# DAC.net
KiCad netlist of a schematic drawn in Altium Designer
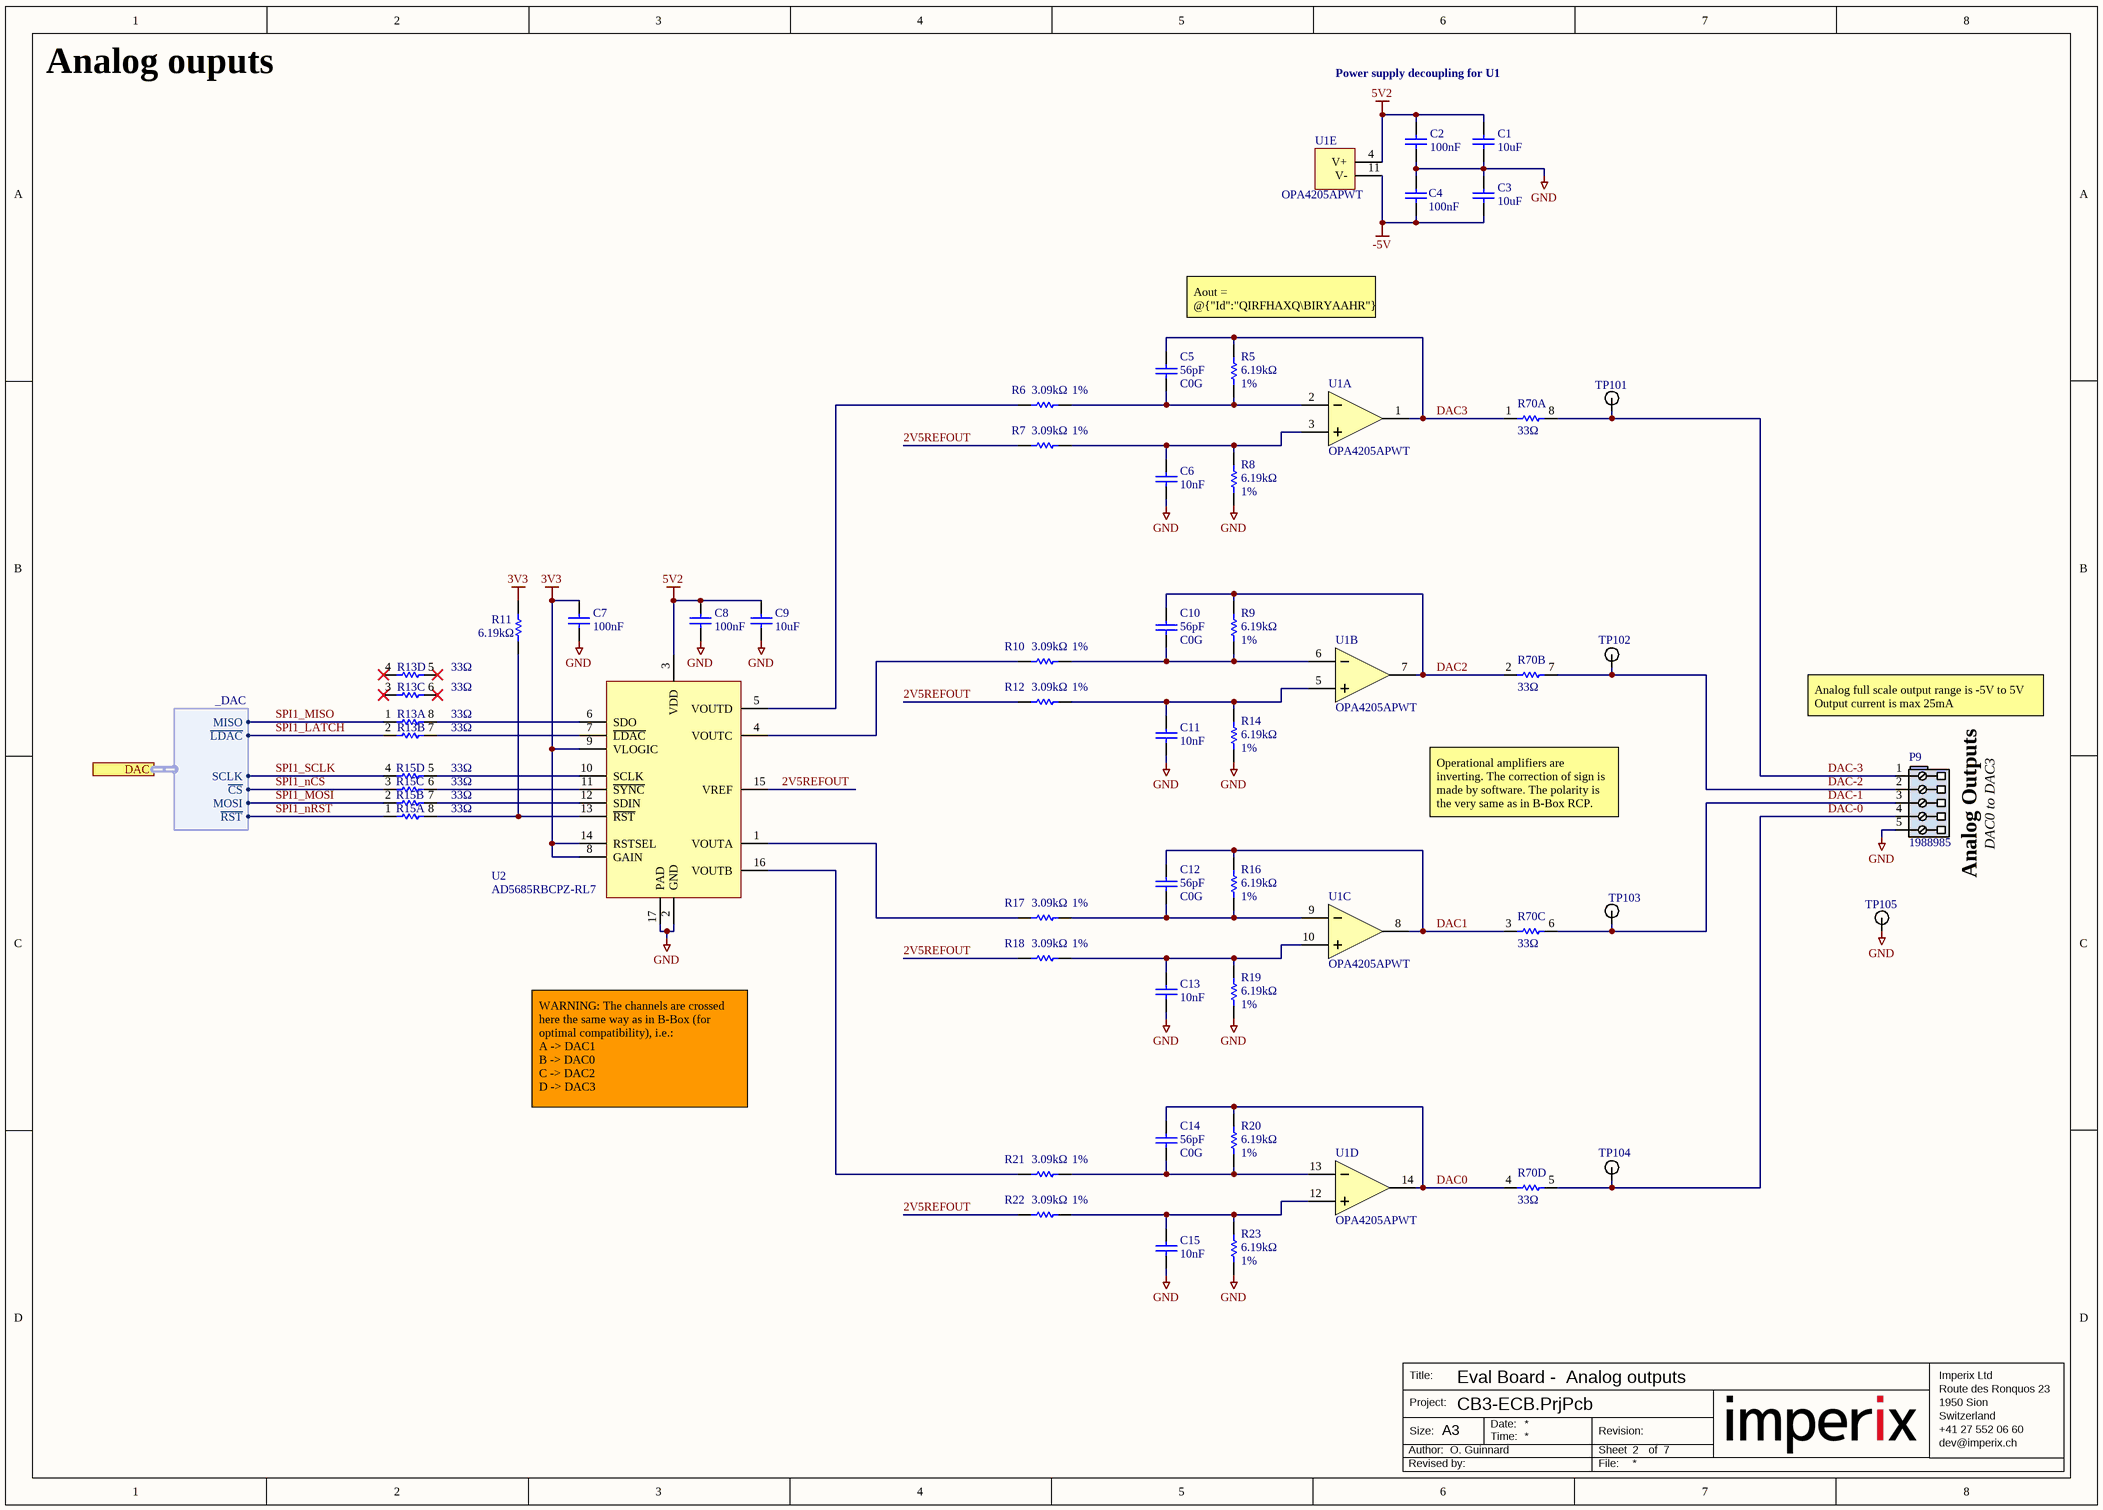
[diagram p0: DAC.SchDoc]

(export (version "E")
  (design (tool "Eeschema 10.0.6"))
  (components
    (comp (ref "C1")
      (value "10uF")
      (footprint "CAPC1608L(0603)")
      (description "CAP CER 10UF 10V X5R 0603 10% (Generic Imperix Component)")
      (fields (field (name "TOLERANCE") "10%") (field (name "Comment") "CAP-10UF-10V-X5R-0603-10%"))
      (libsource (lib "CB3-ECB") (part "Capacitor non-polarized"))
    )
    (comp (ref "C2")
      (value "100nF")
      (footprint "CAPC1005L(0402)")
      (description "CAP CER 100NF 25V X7R 0402 10% (Generic Imperix Component)")
      (fields (field (name "TOLERANCE") "10%") (field (name "Comment") "CAP-100NF-25V-X7R-0402-10%"))
      (libsource (lib "CB3-ECB") (part "Capacitor non-polarized"))
    )
    (comp (ref "C3")
      (value "10uF")
      (footprint "CAPC1608L(0603)")
      (description "CAP CER 10UF 10V X5R 0603 10% (Generic Imperix Component)")
      (fields (field (name "TOLERANCE") "10%") (field (name "Comment") "CAP-10UF-10V-X5R-0603-10%"))
      (libsource (lib "CB3-ECB") (part "Capacitor non-polarized"))
    )
    (comp (ref "C4")
      (value "100nF")
      (footprint "CAPC1005L(0402)")
      (description "CAP CER 100NF 25V X7R 0402 10% (Generic Imperix Component)")
      (fields (field (name "TOLERANCE") "10%") (field (name "Comment") "CAP-100NF-25V-X7R-0402-10%"))
      (libsource (lib "CB3-ECB") (part "Capacitor non-polarized"))
    )
    (comp (ref "C5")
      (value "56pF")
      (footprint "CAPC1005L(0402)")
      (description "CAP CER 56PF 50V C0G 0402 1% (Generic Imperix Component)")
      (fields
        (field (name "TOLERANCE") "1%")
        (field (name "DIELECTRIC") "C0G")
        (field (name "Comment") "CAP-56PF-50V-C0G-0402-1%")
      )
      (libsource (lib "CB3-ECB") (part "Capacitor non-polarized"))
    )
    (comp (ref "C6")
      (value "10nF")
      (footprint "CAPC1005L(0402)")
      (description "CAP CER 10NF 25V X7R 0402 10% (Generic Imperix Component)")
      (fields (field (name "TOLERANCE") "10%") (field (name "Comment") "CAP-10NF-25V-X7R-0402-10%"))
      (libsource (lib "CB3-ECB") (part "Capacitor non-polarized"))
    )
    (comp (ref "C7")
      (value "100nF")
      (footprint "CAPC1005L(0402)")
      (description "CAP CER 100NF 25V X7R 0402 10% (Generic Imperix Component)")
      (fields (field (name "TOLERANCE") "10%") (field (name "Comment") "CAP-100NF-25V-X7R-0402-10%"))
      (libsource (lib "CB3-ECB") (part "Capacitor non-polarized"))
    )
    (comp (ref "C8")
      (value "100nF")
      (footprint "CAPC1005L(0402)")
      (description "CAP CER 100NF 25V X7R 0402 10% (Generic Imperix Component)")
      (fields (field (name "TOLERANCE") "10%") (field (name "Comment") "CAP-100NF-25V-X7R-0402-10%"))
      (libsource (lib "CB3-ECB") (part "Capacitor non-polarized"))
    )
    (comp (ref "C9")
      (value "10uF")
      (footprint "CAPC1608L(0603)")
      (description "CAP CER 10UF 10V X5R 0603 10% (Generic Imperix Component)")
      (fields (field (name "TOLERANCE") "10%") (field (name "Comment") "CAP-10UF-10V-X5R-0603-10%"))
      (libsource (lib "CB3-ECB") (part "Capacitor non-polarized"))
    )
    (comp (ref "C10")
      (value "56pF")
      (footprint "CAPC1005L(0402)")
      (description "CAP CER 56PF 50V C0G 0402 1% (Generic Imperix Component)")
      (fields
        (field (name "TOLERANCE") "1%")
        (field (name "DIELECTRIC") "C0G")
        (field (name "Comment") "CAP-56PF-50V-C0G-0402-1%")
      )
      (libsource (lib "CB3-ECB") (part "Capacitor non-polarized"))
    )
    (comp (ref "C11")
      (value "10nF")
      (footprint "CAPC1005L(0402)")
      (description "CAP CER 10NF 25V X7R 0402 10% (Generic Imperix Component)")
      (fields (field (name "TOLERANCE") "10%") (field (name "Comment") "CAP-10NF-25V-X7R-0402-10%"))
      (libsource (lib "CB3-ECB") (part "Capacitor non-polarized"))
    )
    (comp (ref "C12")
      (value "56pF")
      (footprint "CAPC1005L(0402)")
      (description "CAP CER 56PF 50V C0G 0402 1% (Generic Imperix Component)")
      (fields
        (field (name "TOLERANCE") "1%")
        (field (name "DIELECTRIC") "C0G")
        (field (name "Comment") "CAP-56PF-50V-C0G-0402-1%")
      )
      (libsource (lib "CB3-ECB") (part "Capacitor non-polarized"))
    )
    (comp (ref "C13")
      (value "10nF")
      (footprint "CAPC1005L(0402)")
      (description "CAP CER 10NF 25V X7R 0402 10% (Generic Imperix Component)")
      (fields (field (name "TOLERANCE") "10%") (field (name "Comment") "CAP-10NF-25V-X7R-0402-10%"))
      (libsource (lib "CB3-ECB") (part "Capacitor non-polarized"))
    )
    (comp (ref "C14")
      (value "56pF")
      (footprint "CAPC1005L(0402)")
      (description "CAP CER 56PF 50V C0G 0402 1% (Generic Imperix Component)")
      (fields
        (field (name "TOLERANCE") "1%")
        (field (name "DIELECTRIC") "C0G")
        (field (name "Comment") "CAP-56PF-50V-C0G-0402-1%")
      )
      (libsource (lib "CB3-ECB") (part "Capacitor non-polarized"))
    )
    (comp (ref "C15")
      (value "10nF")
      (footprint "CAPC1005L(0402)")
      (description "CAP CER 10NF 25V X7R 0402 10% (Generic Imperix Component)")
      (fields (field (name "TOLERANCE") "10%") (field (name "Comment") "CAP-10NF-25V-X7R-0402-10%"))
      (libsource (lib "CB3-ECB") (part "Capacitor non-polarized"))
    )
    (comp (ref "P9")
      (value "1988985")
      (footprint "1988985")
      (description "Conn PC Terminal Block 5 POS 3.5mm Solder Thru-Hole 17.5A")
      (fields (field (name "VOLTAGE") "300V"))
      (libsource (lib "CB3-ECB") (part "1988985"))
    )
    (comp (ref "R5")
      (value "6.19kΩ")
      (footprint "RESC1005L(0402)")
      (description "RES SMD 6.19KΩ 1/16W 100PPM 0402 1% (Generic Imperix Component)")
      (fields (field (name "TOLERANCE") "1%") (field (name "Comment") "RES-6.19KΩ-1/16W-100PPM-0402-1%"))
      (libsource (lib "CB3-ECB") (part "Resistor"))
    )
    (comp (ref "R6")
      (value "3.09kΩ")
      (footprint "RESC1005L(0402)")
      (description "RES SMD 3.09KΩ 1/16W 100PPM 0402 1% (Generic Imperix Component)")
      (fields (field (name "TOLERANCE") "1%") (field (name "Comment") "RES-3.09KΩ-1/16W-100PPM-0402-1%"))
      (libsource (lib "CB3-ECB") (part "Resistor"))
    )
    (comp (ref "R7")
      (value "3.09kΩ")
      (footprint "RESC1005L(0402)")
      (description "RES SMD 3.09KΩ 1/16W 100PPM 0402 1% (Generic Imperix Component)")
      (fields (field (name "TOLERANCE") "1%") (field (name "Comment") "RES-3.09KΩ-1/16W-100PPM-0402-1%"))
      (libsource (lib "CB3-ECB") (part "Resistor"))
    )
    (comp (ref "R8")
      (value "6.19kΩ")
      (footprint "RESC1005L(0402)")
      (description "RES SMD 6.19KΩ 1/16W 100PPM 0402 1% (Generic Imperix Component)")
      (fields (field (name "TOLERANCE") "1%") (field (name "Comment") "RES-6.19KΩ-1/16W-100PPM-0402-1%"))
      (libsource (lib "CB3-ECB") (part "Resistor"))
    )
    (comp (ref "R9")
      (value "6.19kΩ")
      (footprint "RESC1005L(0402)")
      (description "RES SMD 6.19KΩ 1/16W 100PPM 0402 1% (Generic Imperix Component)")
      (fields (field (name "TOLERANCE") "1%") (field (name "Comment") "RES-6.19KΩ-1/16W-100PPM-0402-1%"))
      (libsource (lib "CB3-ECB") (part "Resistor"))
    )
    (comp (ref "R10")
      (value "3.09kΩ")
      (footprint "RESC1005L(0402)")
      (description "RES SMD 3.09KΩ 1/16W 100PPM 0402 1% (Generic Imperix Component)")
      (fields (field (name "TOLERANCE") "1%") (field (name "Comment") "RES-3.09KΩ-1/16W-100PPM-0402-1%"))
      (libsource (lib "CB3-ECB") (part "Resistor"))
    )
    (comp (ref "R11")
      (value "6.19kΩ")
      (footprint "RESC1005L(0402)")
      (description "RES SMD 6.19KΩ 1/16W 100PPM 0402 1% (Generic Imperix Component)")
      (fields (field (name "TOLERANCE") "1%") (field (name "Comment") "RES-6.19KΩ-1/16W-100PPM-0402-1%"))
      (libsource (lib "CB3-ECB") (part "Resistor"))
    )
    (comp (ref "R12")
      (value "3.09kΩ")
      (footprint "RESC1005L(0402)")
      (description "RES SMD 3.09KΩ 1/16W 100PPM 0402 1% (Generic Imperix Component)")
      (fields (field (name "TOLERANCE") "1%") (field (name "Comment") "RES-3.09KΩ-1/16W-100PPM-0402-1%"))
      (libsource (lib "CB3-ECB") (part "Resistor"))
    )
    (comp (ref "R13")
      (value "33Ω")
      (footprint "RESQUAD0804")
      (description "Res Thick Film Array 33 Ohm 5% ±200ppm/°C ISOL 8-Pin 0804(4 X 0402) Convex SMD Automotive T/R")
      (fields (field (name "TOLERANCE") "5%") (field (name "Comment") "EXB-28V330JX"))
      (libsource (lib "CB3-ECB") (part "Resistor Array Quad"))
    )
    (comp (ref "R14")
      (value "6.19kΩ")
      (footprint "RESC1005L(0402)")
      (description "RES SMD 6.19KΩ 1/16W 100PPM 0402 1% (Generic Imperix Component)")
      (fields (field (name "TOLERANCE") "1%") (field (name "Comment") "RES-6.19KΩ-1/16W-100PPM-0402-1%"))
      (libsource (lib "CB3-ECB") (part "Resistor"))
    )
    (comp (ref "R15")
      (value "33Ω")
      (footprint "RESQUAD0804")
      (description "Res Thick Film Array 33 Ohm 5% ±200ppm/°C ISOL 8-Pin 0804(4 X 0402) Convex SMD Automotive T/R")
      (fields (field (name "TOLERANCE") "5%") (field (name "Comment") "EXB-28V330JX"))
      (libsource (lib "CB3-ECB") (part "Resistor Array Quad"))
    )
    (comp (ref "R16")
      (value "6.19kΩ")
      (footprint "RESC1005L(0402)")
      (description "RES SMD 6.19KΩ 1/16W 100PPM 0402 1% (Generic Imperix Component)")
      (fields (field (name "TOLERANCE") "1%") (field (name "Comment") "RES-6.19KΩ-1/16W-100PPM-0402-1%"))
      (libsource (lib "CB3-ECB") (part "Resistor"))
    )
    (comp (ref "R17")
      (value "3.09kΩ")
      (footprint "RESC1005L(0402)")
      (description "RES SMD 3.09KΩ 1/16W 100PPM 0402 1% (Generic Imperix Component)")
      (fields (field (name "TOLERANCE") "1%") (field (name "Comment") "RES-3.09KΩ-1/16W-100PPM-0402-1%"))
      (libsource (lib "CB3-ECB") (part "Resistor"))
    )
    (comp (ref "R18")
      (value "3.09kΩ")
      (footprint "RESC1005L(0402)")
      (description "RES SMD 3.09KΩ 1/16W 100PPM 0402 1% (Generic Imperix Component)")
      (fields (field (name "TOLERANCE") "1%") (field (name "Comment") "RES-3.09KΩ-1/16W-100PPM-0402-1%"))
      (libsource (lib "CB3-ECB") (part "Resistor"))
    )
    (comp (ref "R19")
      (value "6.19kΩ")
      (footprint "RESC1005L(0402)")
      (description "RES SMD 6.19KΩ 1/16W 100PPM 0402 1% (Generic Imperix Component)")
      (fields (field (name "TOLERANCE") "1%") (field (name "Comment") "RES-6.19KΩ-1/16W-100PPM-0402-1%"))
      (libsource (lib "CB3-ECB") (part "Resistor"))
    )
    (comp (ref "R20")
      (value "6.19kΩ")
      (footprint "RESC1005L(0402)")
      (description "RES SMD 6.19KΩ 1/16W 100PPM 0402 1% (Generic Imperix Component)")
      (fields (field (name "TOLERANCE") "1%") (field (name "Comment") "RES-6.19KΩ-1/16W-100PPM-0402-1%"))
      (libsource (lib "CB3-ECB") (part "Resistor"))
    )
    (comp (ref "R21")
      (value "3.09kΩ")
      (footprint "RESC1005L(0402)")
      (description "RES SMD 3.09KΩ 1/16W 100PPM 0402 1% (Generic Imperix Component)")
      (fields (field (name "TOLERANCE") "1%") (field (name "Comment") "RES-3.09KΩ-1/16W-100PPM-0402-1%"))
      (libsource (lib "CB3-ECB") (part "Resistor"))
    )
    (comp (ref "R22")
      (value "3.09kΩ")
      (footprint "RESC1005L(0402)")
      (description "RES SMD 3.09KΩ 1/16W 100PPM 0402 1% (Generic Imperix Component)")
      (fields (field (name "TOLERANCE") "1%") (field (name "Comment") "RES-3.09KΩ-1/16W-100PPM-0402-1%"))
      (libsource (lib "CB3-ECB") (part "Resistor"))
    )
    (comp (ref "R23")
      (value "6.19kΩ")
      (footprint "RESC1005L(0402)")
      (description "RES SMD 6.19KΩ 1/16W 100PPM 0402 1% (Generic Imperix Component)")
      (fields (field (name "TOLERANCE") "1%") (field (name "Comment") "RES-6.19KΩ-1/16W-100PPM-0402-1%"))
      (libsource (lib "CB3-ECB") (part "Resistor"))
    )
    (comp (ref "R70")
      (value "33Ω")
      (footprint "RESQUAD0804")
      (description "Res Thick Film Array 33 Ohm 5% ±200ppm/°C ISOL 8-Pin 0804(4 X 0402) Convex SMD Automotive T/R")
      (fields (field (name "TOLERANCE") "5%") (field (name "Comment") "EXB-28V330JX"))
      (libsource (lib "CB3-ECB") (part "Resistor Array Quad"))
    )
    (comp (ref "TP101")
      (value "5001")
      (footprint "5001")
      (description "Black PC Test Point, Miniature Phosphor Bronze Silver Plating Through Hole Mounting Type")
      (libsource (lib "CB3-ECB") (part "Testpoint"))
    )
    (comp (ref "TP102")
      (value "5001")
      (footprint "5001")
      (description "Black PC Test Point, Miniature Phosphor Bronze Silver Plating Through Hole Mounting Type")
      (libsource (lib "CB3-ECB") (part "Testpoint"))
    )
    (comp (ref "TP103")
      (value "5001")
      (footprint "5001")
      (description "Black PC Test Point, Miniature Phosphor Bronze Silver Plating Through Hole Mounting Type")
      (libsource (lib "CB3-ECB") (part "Testpoint"))
    )
    (comp (ref "TP104")
      (value "5001")
      (footprint "5001")
      (description "Black PC Test Point, Miniature Phosphor Bronze Silver Plating Through Hole Mounting Type")
      (libsource (lib "CB3-ECB") (part "Testpoint"))
    )
    (comp (ref "TP105")
      (value "5001")
      (footprint "5001")
      (description "Black PC Test Point, Miniature Phosphor Bronze Silver Plating Through Hole Mounting Type")
      (libsource (lib "CB3-ECB") (part "Testpoint"))
    )
    (comp (ref "U1")
      (value "OPA4205APWT")
      (footprint "TSSOP65P640-14N")
      (libsource (lib "") (part "Quad Op-Amp_1"))
    )
    (comp (ref "U2")
      (value "AD5685RBCPZ-RL7")
      (footprint "QFN50P300X300-16WAL")
      (description "DAC 4-CH Resistor-String 14-bit 16-Pin LFCSP EP T/R")
      (libsource (lib "CB3-ECB") (part "AD5685RBCPZ-RL7"))
    )
  )
  (nets
    (net (code "2") (name "-5V") (class "Default")
      (node (ref "C3") (pin "1") (pinfunction "1_1") (pintype "passive"))
      (node (ref "C4") (pin "1") (pinfunction "1_1") (pintype "passive"))
      (node (ref "U1") (pin "11") (pinfunction "V-_11") (pintype "power_in"))
    )
    (net (code "3") (name "/2V5REFOUT") (class "Default")
      (node (ref "R12") (pin "2") (pinfunction "2_2") (pintype "passive"))
      (node (ref "R18") (pin "2") (pinfunction "2_2") (pintype "passive"))
      (node (ref "R22") (pin "2") (pinfunction "2_2") (pintype "passive"))
      (node (ref "R7") (pin "2") (pinfunction "2_2") (pintype "passive"))
      (node (ref "U2") (pin "15") (pinfunction "VREF_15") (pintype "passive"))
    )
    (net (code "4") (name "/DAC-0") (class "Default")
      (node (ref "P9") (pin "4") (pinfunction "4_4") (pintype "passive"))
      (node (ref "R70") (pin "5") (pinfunction "5_5") (pintype "passive"))
      (node (ref "TP104") (pin "1") (pinfunction "TP_1") (pintype "passive"))
    )
    (net (code "5") (name "/DAC-1") (class "Default")
      (node (ref "P9") (pin "3") (pinfunction "3_3") (pintype "passive"))
      (node (ref "R70") (pin "6") (pinfunction "6_6") (pintype "passive"))
      (node (ref "TP103") (pin "1") (pinfunction "TP_1") (pintype "passive"))
    )
    (net (code "6") (name "/DAC-2") (class "Default")
      (node (ref "P9") (pin "2") (pinfunction "2_2") (pintype "passive"))
      (node (ref "R70") (pin "7") (pinfunction "7_7") (pintype "passive"))
      (node (ref "TP102") (pin "1") (pinfunction "TP_1") (pintype "passive"))
    )
    (net (code "7") (name "/DAC-3") (class "Default")
      (node (ref "P9") (pin "1") (pinfunction "1_1") (pintype "passive"))
      (node (ref "R70") (pin "8") (pinfunction "8_8") (pintype "passive"))
      (node (ref "TP101") (pin "1") (pinfunction "TP_1") (pintype "passive"))
    )
    (net (code "8") (name "/DAC0") (class "Default")
      (node (ref "C14") (pin "2") (pinfunction "2_2") (pintype "passive"))
      (node (ref "R20") (pin "2") (pinfunction "2_2") (pintype "passive"))
      (node (ref "R70") (pin "4") (pinfunction "4_4") (pintype "passive"))
      (node (ref "U1") (pin "14") (pinfunction "OUT_14") (pintype "passive"))
    )
    (net (code "9") (name "/DAC1") (class "Default")
      (node (ref "C12") (pin "2") (pinfunction "2_2") (pintype "passive"))
      (node (ref "R16") (pin "2") (pinfunction "2_2") (pintype "passive"))
      (node (ref "R70") (pin "3") (pinfunction "3_3") (pintype "passive"))
      (node (ref "U1") (pin "8") (pinfunction "OUT_8") (pintype "passive"))
    )
    (net (code "10") (name "/DAC2") (class "Default")
      (node (ref "C10") (pin "2") (pinfunction "2_2") (pintype "passive"))
      (node (ref "R70") (pin "2") (pinfunction "2_2") (pintype "passive"))
      (node (ref "R9") (pin "2") (pinfunction "2_2") (pintype "passive"))
      (node (ref "U1") (pin "7") (pinfunction "OUT_7") (pintype "passive"))
    )
    (net (code "11") (name "/DAC3") (class "Default")
      (node (ref "C5") (pin "2") (pinfunction "2_2") (pintype "passive"))
      (node (ref "R5") (pin "2") (pinfunction "2_2") (pintype "passive"))
      (node (ref "R70") (pin "1") (pinfunction "1_1") (pintype "passive"))
      (node (ref "U1") (pin "1") (pinfunction "OUT_1") (pintype "passive"))
    )
    (net (code "12") (name "/SPI1_LATCH") (class "Default")
      (node (ref "R13") (pin "2") (pinfunction "2_2") (pintype "passive"))
    )
    (net (code "13") (name "/SPI1_MISO") (class "Default")
      (node (ref "R13") (pin "1") (pinfunction "1_1") (pintype "passive"))
    )
    (net (code "14") (name "/SPI1_MOSI") (class "Default")
      (node (ref "R15") (pin "2") (pinfunction "2_2") (pintype "passive"))
    )
    (net (code "15") (name "/SPI1_SCLK") (class "Default")
      (node (ref "R15") (pin "4") (pinfunction "4_4") (pintype "passive"))
    )
    (net (code "16") (name "/SPI1_nCS") (class "Default")
      (node (ref "R15") (pin "3") (pinfunction "3_3") (pintype "passive"))
    )
    (net (code "17") (name "/SPI1_nRST") (class "Default")
      (node (ref "R15") (pin "1") (pinfunction "1_1") (pintype "passive"))
    )
    (net (code "19") (name "3V3") (class "Default")
      (node (ref "C7") (pin "2") (pinfunction "2_2") (pintype "passive"))
      (node (ref "R11") (pin "2") (pinfunction "2_2") (pintype "passive"))
      (node (ref "U2") (pin "14") (pinfunction "RSTSEL_14") (pintype "passive"))
      (node (ref "U2") (pin "8") (pinfunction "GAIN_8") (pintype "passive"))
      (node (ref "U2") (pin "9") (pinfunction "VLOGIC_9") (pintype "passive"))
    )
    (net (code "20") (name "5V2") (class "Default")
      (node (ref "C1") (pin "2") (pinfunction "2_2") (pintype "passive"))
      (node (ref "C2") (pin "2") (pinfunction "2_2") (pintype "passive"))
      (node (ref "C8") (pin "2") (pinfunction "2_2") (pintype "passive"))
      (node (ref "C9") (pin "2") (pinfunction "2_2") (pintype "passive"))
      (node (ref "U1") (pin "4") (pinfunction "V+_4") (pintype "power_in"))
      (node (ref "U2") (pin "3") (pinfunction "VDD_3") (pintype "passive"))
    )
    (net (code "21") (name "GND") (class "Default")
      (node (ref "C1") (pin "1") (pinfunction "1_1") (pintype "passive"))
      (node (ref "C11") (pin "1") (pinfunction "1_1") (pintype "passive"))
      (node (ref "C13") (pin "1") (pinfunction "1_1") (pintype "passive"))
      (node (ref "C15") (pin "1") (pinfunction "1_1") (pintype "passive"))
      (node (ref "C2") (pin "1") (pinfunction "1_1") (pintype "passive"))
      (node (ref "C3") (pin "2") (pinfunction "2_2") (pintype "passive"))
      (node (ref "C4") (pin "2") (pinfunction "2_2") (pintype "passive"))
      (node (ref "C6") (pin "1") (pinfunction "1_1") (pintype "passive"))
      (node (ref "C7") (pin "1") (pinfunction "1_1") (pintype "passive"))
      (node (ref "C8") (pin "1") (pinfunction "1_1") (pintype "passive"))
      (node (ref "C9") (pin "1") (pinfunction "1_1") (pintype "passive"))
      (node (ref "P9") (pin "5") (pinfunction "5_5") (pintype "passive"))
      (node (ref "R14") (pin "1") (pinfunction "1_1") (pintype "passive"))
      (node (ref "R19") (pin "1") (pinfunction "1_1") (pintype "passive"))
      (node (ref "R23") (pin "1") (pinfunction "1_1") (pintype "passive"))
      (node (ref "R8") (pin "1") (pinfunction "1_1") (pintype "passive"))
      (node (ref "TP105") (pin "1") (pinfunction "TP_1") (pintype "passive"))
      (node (ref "U2") (pin "17") (pinfunction "PAD_17") (pintype "passive"))
      (node (ref "U2") (pin "2") (pinfunction "GND_2") (pintype "passive"))
    )
    (net (code "22") (name "Net-(U1A-IN+)") (class "Default")
      (node (ref "C6") (pin "2") (pinfunction "2_2") (pintype "passive"))
      (node (ref "R7") (pin "1") (pinfunction "1_1") (pintype "passive"))
      (node (ref "R8") (pin "2") (pinfunction "2_2") (pintype "passive"))
      (node (ref "U1") (pin "3") (pinfunction "IN+_3") (pintype "passive"))
    )
    (net (code "23") (name "Net-(U1A-IN-)") (class "Default")
      (node (ref "C5") (pin "1") (pinfunction "1_1") (pintype "passive"))
      (node (ref "R5") (pin "1") (pinfunction "1_1") (pintype "passive"))
      (node (ref "R6") (pin "1") (pinfunction "1_1") (pintype "passive"))
      (node (ref "U1") (pin "2") (pinfunction "IN-_2") (pintype "passive"))
    )
    (net (code "24") (name "Net-(U1B-IN+)") (class "Default")
      (node (ref "C11") (pin "2") (pinfunction "2_2") (pintype "passive"))
      (node (ref "R12") (pin "1") (pinfunction "1_1") (pintype "passive"))
      (node (ref "R14") (pin "2") (pinfunction "2_2") (pintype "passive"))
      (node (ref "U1") (pin "5") (pinfunction "IN+_5") (pintype "passive"))
    )
    (net (code "25") (name "Net-(U1B-IN-)") (class "Default")
      (node (ref "C10") (pin "1") (pinfunction "1_1") (pintype "passive"))
      (node (ref "R10") (pin "1") (pinfunction "1_1") (pintype "passive"))
      (node (ref "R9") (pin "1") (pinfunction "1_1") (pintype "passive"))
      (node (ref "U1") (pin "6") (pinfunction "IN-_6") (pintype "passive"))
    )
    (net (code "26") (name "Net-(U1C-IN+)") (class "Default")
      (node (ref "C13") (pin "2") (pinfunction "2_2") (pintype "passive"))
      (node (ref "R18") (pin "1") (pinfunction "1_1") (pintype "passive"))
      (node (ref "R19") (pin "2") (pinfunction "2_2") (pintype "passive"))
      (node (ref "U1") (pin "10") (pinfunction "IN+_10") (pintype "passive"))
    )
    (net (code "27") (name "Net-(U1C-IN-)") (class "Default")
      (node (ref "C12") (pin "1") (pinfunction "1_1") (pintype "passive"))
      (node (ref "R16") (pin "1") (pinfunction "1_1") (pintype "passive"))
      (node (ref "R17") (pin "1") (pinfunction "1_1") (pintype "passive"))
      (node (ref "U1") (pin "9") (pinfunction "IN-_9") (pintype "passive"))
    )
    (net (code "28") (name "Net-(U1D-IN+)") (class "Default")
      (node (ref "C15") (pin "2") (pinfunction "2_2") (pintype "passive"))
      (node (ref "R22") (pin "1") (pinfunction "1_1") (pintype "passive"))
      (node (ref "R23") (pin "2") (pinfunction "2_2") (pintype "passive"))
      (node (ref "U1") (pin "12") (pinfunction "IN+_12") (pintype "passive"))
    )
    (net (code "29") (name "Net-(U1D-IN-)") (class "Default")
      (node (ref "C14") (pin "1") (pinfunction "1_1") (pintype "passive"))
      (node (ref "R20") (pin "1") (pinfunction "1_1") (pintype "passive"))
      (node (ref "R21") (pin "1") (pinfunction "1_1") (pintype "passive"))
      (node (ref "U1") (pin "13") (pinfunction "IN-_13") (pintype "passive"))
    )
    (net (code "30") (name "Net-(U2-SCLK)") (class "Default")
      (node (ref "R15") (pin "5") (pinfunction "5_5") (pintype "passive"))
      (node (ref "U2") (pin "10") (pinfunction "SCLK_10") (pintype "passive"))
    )
    (net (code "31") (name "Net-(U2-SDIN)") (class "Default")
      (node (ref "R15") (pin "7") (pinfunction "7_7") (pintype "passive"))
      (node (ref "U2") (pin "12") (pinfunction "SDIN_12") (pintype "passive"))
    )
    (net (code "32") (name "Net-(U2-SDO)") (class "Default")
      (node (ref "R13") (pin "8") (pinfunction "8_8") (pintype "passive"))
      (node (ref "U2") (pin "6") (pinfunction "SDO_6") (pintype "passive"))
    )
    (net (code "33") (name "Net-(U2-VOUTA)") (class "Default")
      (node (ref "R17") (pin "2") (pinfunction "2_2") (pintype "passive"))
      (node (ref "U2") (pin "1") (pinfunction "VOUTA_1") (pintype "passive"))
    )
    (net (code "34") (name "Net-(U2-VOUTB)") (class "Default")
      (node (ref "R21") (pin "2") (pinfunction "2_2") (pintype "passive"))
      (node (ref "U2") (pin "16") (pinfunction "VOUTB_16") (pintype "passive"))
    )
    (net (code "35") (name "Net-(U2-VOUTC)") (class "Default")
      (node (ref "R10") (pin "2") (pinfunction "2_2") (pintype "passive"))
      (node (ref "U2") (pin "4") (pinfunction "VOUTC_4") (pintype "passive"))
    )
    (net (code "36") (name "Net-(U2-VOUTD)") (class "Default")
      (node (ref "R6") (pin "2") (pinfunction "2_2") (pintype "passive"))
      (node (ref "U2") (pin "5") (pinfunction "VOUTD_5") (pintype "passive"))
    )
    (net (code "37") (name "Net-(U2-~{LDAC})") (class "Default")
      (node (ref "R13") (pin "7") (pinfunction "7_7") (pintype "passive"))
      (node (ref "U2") (pin "7") (pinfunction "~{LDAC}_7") (pintype "passive"))
    )
    (net (code "38") (name "Net-(U2-~{RST})") (class "Default")
      (node (ref "R11") (pin "1") (pinfunction "1_1") (pintype "passive"))
      (node (ref "R15") (pin "8") (pinfunction "8_8") (pintype "passive"))
      (node (ref "U2") (pin "13") (pinfunction "~{RST}_13") (pintype "passive"))
    )
    (net (code "39") (name "Net-(U2-~{SYNC})") (class "Default")
      (node (ref "R15") (pin "6") (pinfunction "6_6") (pintype "passive"))
      (node (ref "U2") (pin "11") (pinfunction "~{SYNC}_11") (pintype "passive"))
    )
    (net (code "40") (name "unconnected-(R13-Pad3)") (class "Default")
      (node (ref "R13") (pin "3") (pinfunction "3_3") (pintype "passive+no_connect"))
    )
    (net (code "41") (name "unconnected-(R13-Pad4)") (class "Default")
      (node (ref "R13") (pin "4") (pinfunction "4_4") (pintype "passive+no_connect"))
    )
    (net (code "42") (name "unconnected-(R13-Pad5)") (class "Default")
      (node (ref "R13") (pin "5") (pinfunction "5_5") (pintype "passive+no_connect"))
    )
    (net (code "43") (name "unconnected-(R13-Pad6)") (class "Default")
      (node (ref "R13") (pin "6") (pinfunction "6_6") (pintype "passive+no_connect"))
    )
  )
)
